# MarsCarrier_PWR.net
KiCad netlist of a schematic drawn in Altium Designer
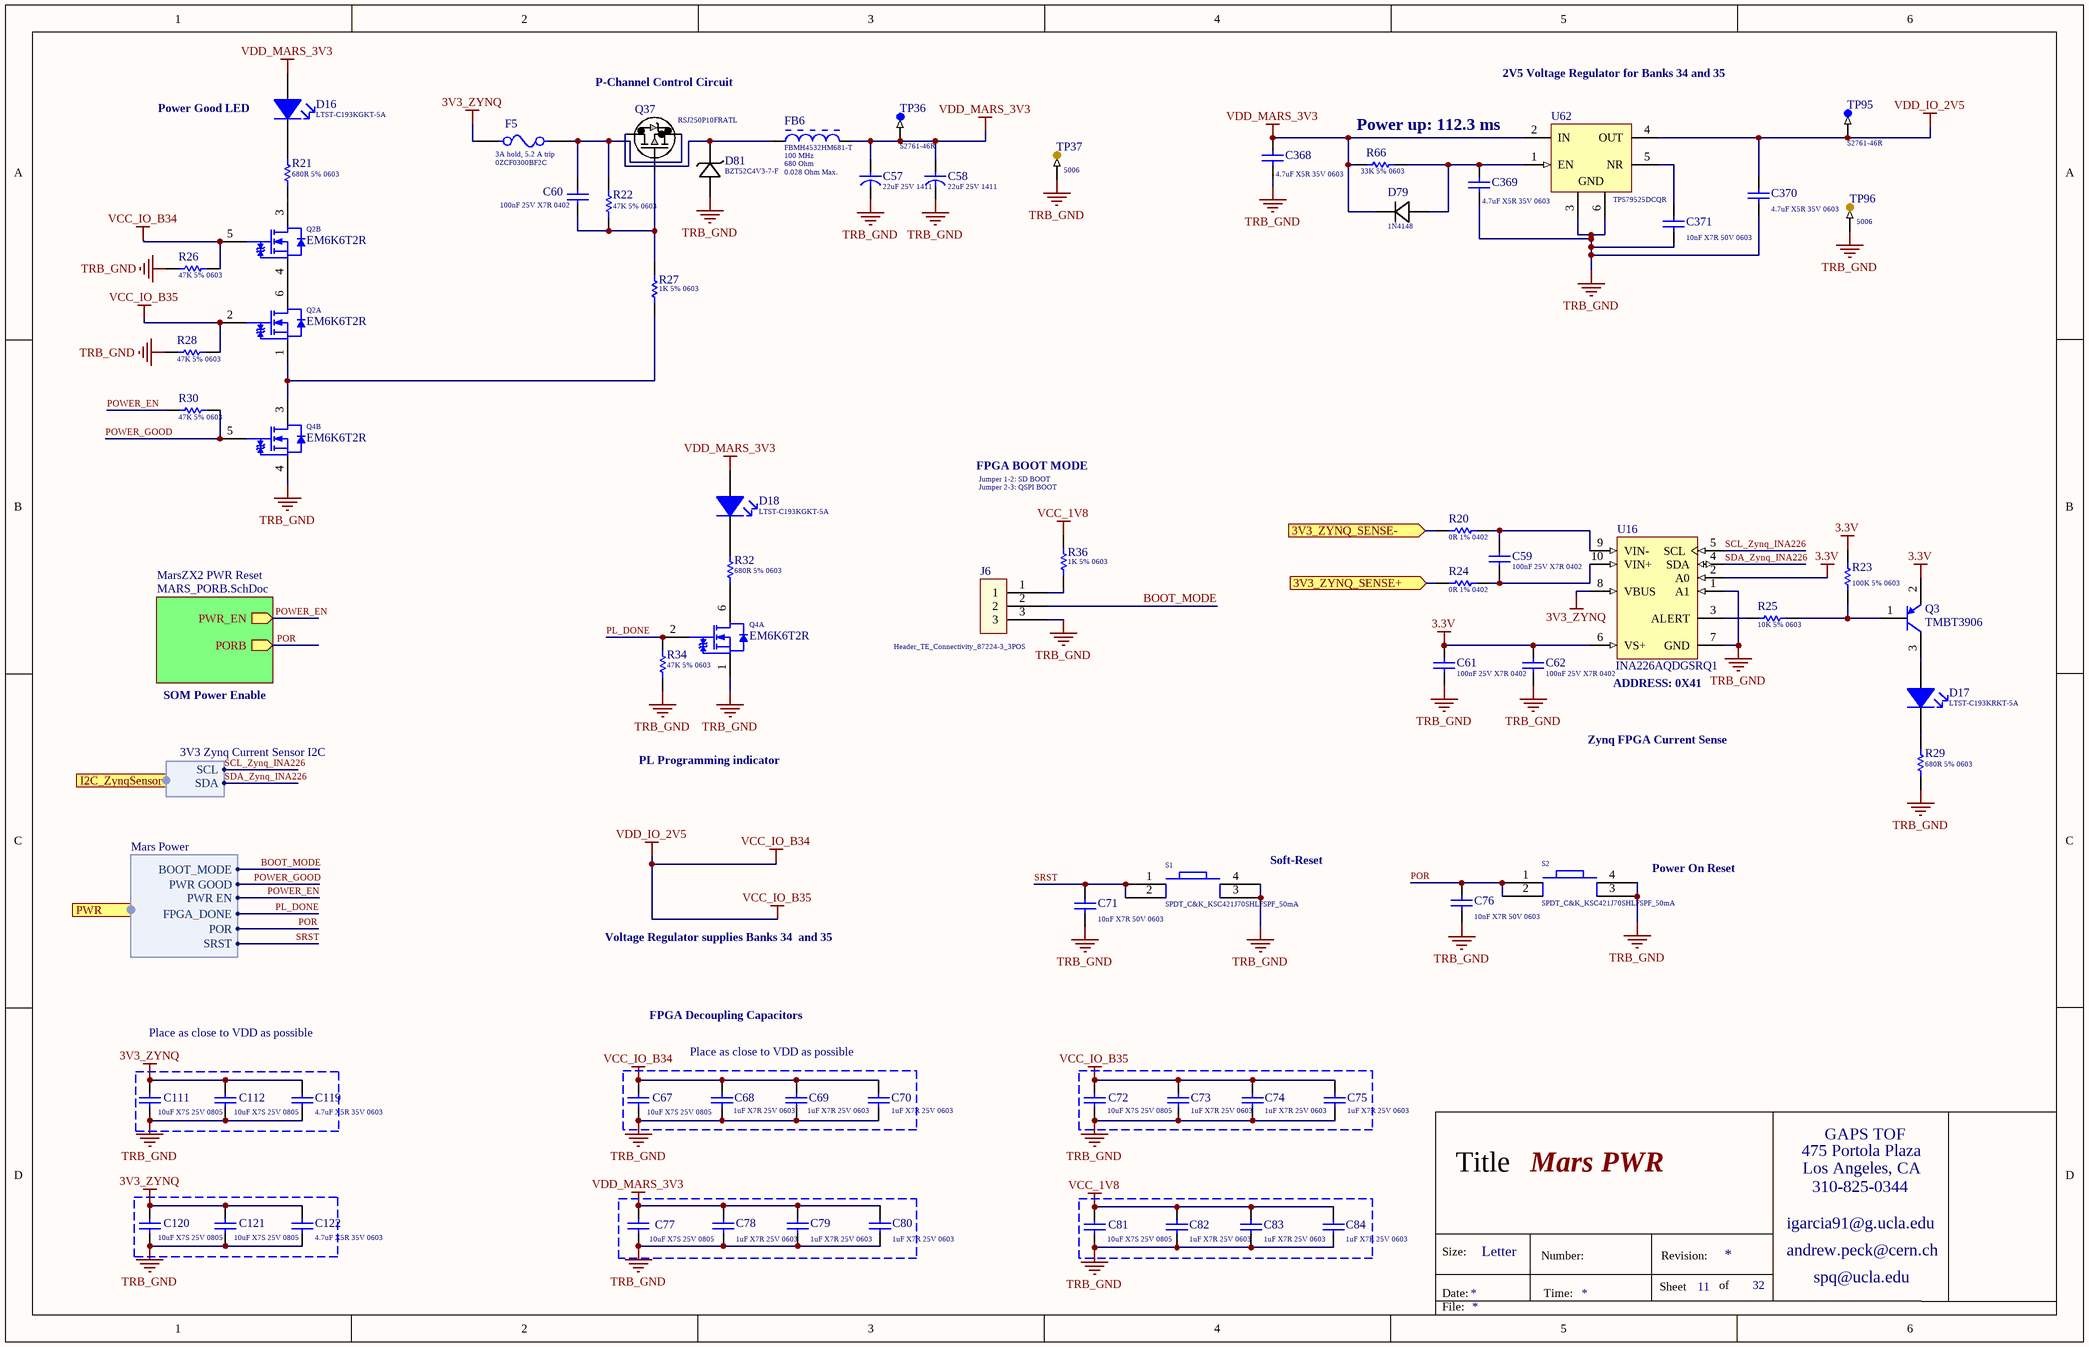
[diagram p0: MarsCarrier_PWR.SchDoc]

(export (version "E")
  (design (tool "Eeschema 10.0.6"))
  (components
    (comp (ref "C57")
      (value "Cap_Kemet_T521B226M025ATE100_22uF")
      (footprint "Cap_Kemet_T521B226M025ATE100_22uF")
      (description "Tantalum Capacitors - Polymer SMD 25V 22uF 1311 20% ESR=100mOhms")
      (fields (field (name "CAPACITANCE") "22uF 25V 1411"))
      (libsource (lib "Cap_Kemet_T521B226M025ATE100_22uF") (part "Cap_Kemet_T521B226M025ATE100_22uF"))
    )
    (comp (ref "C58")
      (value "Cap_Kemet_T521B226M025ATE100_22uF")
      (footprint "Cap_Kemet_T521B226M025ATE100_22uF")
      (description "Tantalum Capacitors - Polymer SMD 25V 22uF 1311 20% ESR=100mOhms")
      (fields (field (name "CAPACITANCE") "22uF 25V 1411"))
      (libsource (lib "Cap_Kemet_T521B226M025ATE100_22uF") (part "Cap_Kemet_T521B226M025ATE100_22uF"))
    )
    (comp (ref "C59")
      (value "Cap_Taiyo_Yuden_TMK105B7104KV-FR_100nF")
      (footprint "Cap_Taiyo_Yuden_TMK105B7104KV-FR_100nF")
      (description "CAP CER 100nF 25V X7R 0402")
      (fields (field (name "CAPACITANCE") "100nF 25V X7R 0402"))
      (libsource (lib "Cap_Taiyo_Yuden_TMK105B7104KV-FR_100nF") (part "Cap_Taiyo_Yuden_TMK105B7104KV-FR_100nF"))
    )
    (comp (ref "C60")
      (value "Cap_Taiyo_Yuden_TMK105B7104KV-FR_100nF")
      (footprint "Cap_Taiyo_Yuden_TMK105B7104KV-FR_100nF")
      (description "CAP CER 100nF 25V X7R 0402")
      (fields (field (name "CAPACITANCE") "100nF 25V X7R 0402"))
      (libsource (lib "Cap_Taiyo_Yuden_TMK105B7104KV-FR_100nF") (part "Cap_Taiyo_Yuden_TMK105B7104KV-FR_100nF"))
    )
    (comp (ref "C61")
      (value "Cap_Taiyo_Yuden_TMK105B7104KV-FR_100nF")
      (footprint "Cap_Taiyo_Yuden_TMK105B7104KV-FR_100nF")
      (description "CAP CER 100nF 25V X7R 0402")
      (fields (field (name "CAPACITANCE") "100nF 25V X7R 0402"))
      (libsource (lib "Cap_Taiyo_Yuden_TMK105B7104KV-FR_100nF") (part "Cap_Taiyo_Yuden_TMK105B7104KV-FR_100nF"))
    )
    (comp (ref "C62")
      (value "Cap_Taiyo_Yuden_TMK105B7104KV-FR_100nF")
      (footprint "Cap_Taiyo_Yuden_TMK105B7104KV-FR_100nF")
      (description "CAP CER 100nF 25V X7R 0402")
      (fields (field (name "CAPACITANCE") "100nF 25V X7R 0402"))
      (libsource (lib "Cap_Taiyo_Yuden_TMK105B7104KV-FR_100nF") (part "Cap_Taiyo_Yuden_TMK105B7104KV-FR_100nF"))
    )
    (comp (ref "C67")
      (value "Cap_Murata_ GRM21BC71E106ME11L_10uF")
      (footprint "Cap_Murata_ GRM21BC71E106ME11L_10uF")
      (description "CAP CER 10uF 25V X7R 0805")
      (fields (field (name "CAPACITANCE") "10uF X7S 25V 0805"))
      (libsource (lib "Cap_Murata_ GRM21BC71E106ME11L_10uF") (part "Cap_Murata_ GRM21BC71E106ME11L_10uF"))
    )
    (comp (ref "C68")
      (value "Cap_Murata_GCJ188R71E105KA01J_1uF")
      (footprint "Cap_Murata_GCJ188R71E105KA01J_1uF")
      (description "CAP CER 1uF 25V X7R 0603")
      (fields (field (name "CAPACITANCE") "1uF X7R 25V 0603"))
      (libsource (lib "Cap_Murata_GCJ188R71E105KA01J_1uF") (part "Cap_Murata_GCJ188R71E105KA01J_1uF"))
    )
    (comp (ref "C69")
      (value "Cap_Murata_GCJ188R71E105KA01J_1uF")
      (footprint "Cap_Murata_GCJ188R71E105KA01J_1uF")
      (description "CAP CER 1uF 25V X7R 0603")
      (fields (field (name "CAPACITANCE") "1uF X7R 25V 0603"))
      (libsource (lib "Cap_Murata_GCJ188R71E105KA01J_1uF") (part "Cap_Murata_GCJ188R71E105KA01J_1uF"))
    )
    (comp (ref "C70")
      (value "Cap_Murata_GCJ188R71E105KA01J_1uF")
      (footprint "Cap_Murata_GCJ188R71E105KA01J_1uF")
      (description "CAP CER 1uF 25V X7R 0603")
      (fields (field (name "CAPACITANCE") "1uF X7R 25V 0603"))
      (libsource (lib "Cap_Murata_GCJ188R71E105KA01J_1uF") (part "Cap_Murata_GCJ188R71E105KA01J_1uF"))
    )
    (comp (ref "C71")
      (value "Cap_Kemet_C0603C103J5RACTU_eec")
      (footprint "Kemet_C0603_0")
      (description "CAP CER 10nF 50V X7R 0603")
      (fields
        (field (name "PART NUMBER") "C0603C103J5RACTU")
        (field (name "MANUFACTURER") "Kemet")
        (field (name "CAPACITANCE") "10nF X7R 50V 0603")
      )
      (libsource (lib "Cap_Kemet_C0603C103J5RACTU_10nF") (part "Cap_Kemet_C0603C103J5RACTU_eec"))
    )
    (comp (ref "C72")
      (value "Cap_Murata_ GRM21BC71E106ME11L_10uF")
      (footprint "Cap_Murata_ GRM21BC71E106ME11L_10uF")
      (description "CAP CER 10uF 25V X7R 0805")
      (fields (field (name "CAPACITANCE") "10uF X7S 25V 0805"))
      (libsource (lib "Cap_Murata_ GRM21BC71E106ME11L_10uF") (part "Cap_Murata_ GRM21BC71E106ME11L_10uF"))
    )
    (comp (ref "C73")
      (value "Cap_Murata_GCJ188R71E105KA01J_1uF")
      (footprint "Cap_Murata_GCJ188R71E105KA01J_1uF")
      (description "CAP CER 1uF 25V X7R 0603")
      (fields (field (name "CAPACITANCE") "1uF X7R 25V 0603"))
      (libsource (lib "Cap_Murata_GCJ188R71E105KA01J_1uF") (part "Cap_Murata_GCJ188R71E105KA01J_1uF"))
    )
    (comp (ref "C74")
      (value "Cap_Murata_GCJ188R71E105KA01J_1uF")
      (footprint "Cap_Murata_GCJ188R71E105KA01J_1uF")
      (description "CAP CER 1uF 25V X7R 0603")
      (fields (field (name "CAPACITANCE") "1uF X7R 25V 0603"))
      (libsource (lib "Cap_Murata_GCJ188R71E105KA01J_1uF") (part "Cap_Murata_GCJ188R71E105KA01J_1uF"))
    )
    (comp (ref "C75")
      (value "Cap_Murata_GCJ188R71E105KA01J_1uF")
      (footprint "Cap_Murata_GCJ188R71E105KA01J_1uF")
      (description "CAP CER 1uF 25V X7R 0603")
      (fields (field (name "CAPACITANCE") "1uF X7R 25V 0603"))
      (libsource (lib "Cap_Murata_GCJ188R71E105KA01J_1uF") (part "Cap_Murata_GCJ188R71E105KA01J_1uF"))
    )
    (comp (ref "C76")
      (value "Cap_Kemet_C0603C103J5RACTU_eec")
      (footprint "Kemet_C0603_0")
      (description "CAP CER 10nF 50V X7R 0603")
      (fields
        (field (name "PART NUMBER") "C0603C103J5RACTU")
        (field (name "MANUFACTURER") "Kemet")
        (field (name "CAPACITANCE") "10nF X7R 50V 0603")
      )
      (libsource (lib "Cap_Kemet_C0603C103J5RACTU_10nF") (part "Cap_Kemet_C0603C103J5RACTU_eec"))
    )
    (comp (ref "C77")
      (value "Cap_Murata_ GRM21BC71E106ME11L_10uF")
      (footprint "Cap_Murata_ GRM21BC71E106ME11L_10uF")
      (description "CAP CER 10uF 25V X7R 0805")
      (fields (field (name "CAPACITANCE") "10uF X7S 25V 0805"))
      (libsource (lib "Cap_Murata_ GRM21BC71E106ME11L_10uF") (part "Cap_Murata_ GRM21BC71E106ME11L_10uF"))
    )
    (comp (ref "C78")
      (value "Cap_Murata_GCJ188R71E105KA01J_1uF")
      (footprint "Cap_Murata_GCJ188R71E105KA01J_1uF")
      (description "CAP CER 1uF 25V X7R 0603")
      (fields (field (name "CAPACITANCE") "1uF X7R 25V 0603"))
      (libsource (lib "Cap_Murata_GCJ188R71E105KA01J_1uF") (part "Cap_Murata_GCJ188R71E105KA01J_1uF"))
    )
    (comp (ref "C79")
      (value "Cap_Murata_GCJ188R71E105KA01J_1uF")
      (footprint "Cap_Murata_GCJ188R71E105KA01J_1uF")
      (description "CAP CER 1uF 25V X7R 0603")
      (fields (field (name "CAPACITANCE") "1uF X7R 25V 0603"))
      (libsource (lib "Cap_Murata_GCJ188R71E105KA01J_1uF") (part "Cap_Murata_GCJ188R71E105KA01J_1uF"))
    )
    (comp (ref "C80")
      (value "Cap_Murata_GCJ188R71E105KA01J_1uF")
      (footprint "Cap_Murata_GCJ188R71E105KA01J_1uF")
      (description "CAP CER 1uF 25V X7R 0603")
      (fields (field (name "CAPACITANCE") "1uF X7R 25V 0603"))
      (libsource (lib "Cap_Murata_GCJ188R71E105KA01J_1uF") (part "Cap_Murata_GCJ188R71E105KA01J_1uF"))
    )
    (comp (ref "C81")
      (value "Cap_Murata_ GRM21BC71E106ME11L_10uF")
      (footprint "Cap_Murata_ GRM21BC71E106ME11L_10uF")
      (description "CAP CER 10uF 25V X7R 0805")
      (fields (field (name "CAPACITANCE") "10uF X7S 25V 0805"))
      (libsource (lib "Cap_Murata_ GRM21BC71E106ME11L_10uF") (part "Cap_Murata_ GRM21BC71E106ME11L_10uF"))
    )
    (comp (ref "C82")
      (value "Cap_Murata_GCJ188R71E105KA01J_1uF")
      (footprint "Cap_Murata_GCJ188R71E105KA01J_1uF")
      (description "CAP CER 1uF 25V X7R 0603")
      (fields (field (name "CAPACITANCE") "1uF X7R 25V 0603"))
      (libsource (lib "Cap_Murata_GCJ188R71E105KA01J_1uF") (part "Cap_Murata_GCJ188R71E105KA01J_1uF"))
    )
    (comp (ref "C83")
      (value "Cap_Murata_GCJ188R71E105KA01J_1uF")
      (footprint "Cap_Murata_GCJ188R71E105KA01J_1uF")
      (description "CAP CER 1uF 25V X7R 0603")
      (fields (field (name "CAPACITANCE") "1uF X7R 25V 0603"))
      (libsource (lib "Cap_Murata_GCJ188R71E105KA01J_1uF") (part "Cap_Murata_GCJ188R71E105KA01J_1uF"))
    )
    (comp (ref "C84")
      (value "Cap_Murata_GCJ188R71E105KA01J_1uF")
      (footprint "Cap_Murata_GCJ188R71E105KA01J_1uF")
      (description "CAP CER 1uF 25V X7R 0603")
      (fields (field (name "CAPACITANCE") "1uF X7R 25V 0603"))
      (libsource (lib "Cap_Murata_GCJ188R71E105KA01J_1uF") (part "Cap_Murata_GCJ188R71E105KA01J_1uF"))
    )
    (comp (ref "C111")
      (value "Cap_Murata_ GRM21BC71E106ME11L_10uF")
      (footprint "Cap_Murata_ GRM21BC71E106ME11L_10uF")
      (description "CAP CER 10uF 25V X7R 0805")
      (fields (field (name "CAPACITANCE") "10uF X7S 25V 0805"))
      (libsource (lib "Cap_Murata_ GRM21BC71E106ME11L_10uF") (part "Cap_Murata_ GRM21BC71E106ME11L_10uF"))
    )
    (comp (ref "C112")
      (value "Cap_Murata_ GRM21BC71E106ME11L_10uF")
      (footprint "Cap_Murata_ GRM21BC71E106ME11L_10uF")
      (description "CAP CER 10uF 25V X7R 0805")
      (fields (field (name "CAPACITANCE") "10uF X7S 25V 0805"))
      (libsource (lib "Cap_Murata_ GRM21BC71E106ME11L_10uF") (part "Cap_Murata_ GRM21BC71E106ME11L_10uF"))
    )
    (comp (ref "C119")
      (value "Cap_Murata_ZRB18AR6YA475ME05L_4.7uF")
      (footprint "Cap_Murata_ZRB18AR6YA475ME05L_4.7uF")
      (description "CAP CER 4.7uF 35V X5R 0603")
      (fields (field (name "CAPACITANCE") "4.7uF X5R 35V 0603"))
      (libsource (lib "Cap_Murata_ZRB18AR6YA475ME05L_4.7uF") (part "Cap_Murata_ZRB18AR6YA475ME05L_4.7uF"))
    )
    (comp (ref "C120")
      (value "Cap_Murata_ GRM21BC71E106ME11L_10uF")
      (footprint "Cap_Murata_ GRM21BC71E106ME11L_10uF")
      (description "CAP CER 10uF 25V X7R 0805")
      (fields (field (name "CAPACITANCE") "10uF X7S 25V 0805"))
      (libsource (lib "Cap_Murata_ GRM21BC71E106ME11L_10uF") (part "Cap_Murata_ GRM21BC71E106ME11L_10uF"))
    )
    (comp (ref "C121")
      (value "Cap_Murata_ GRM21BC71E106ME11L_10uF")
      (footprint "Cap_Murata_ GRM21BC71E106ME11L_10uF")
      (description "CAP CER 10uF 25V X7R 0805")
      (fields (field (name "CAPACITANCE") "10uF X7S 25V 0805"))
      (libsource (lib "Cap_Murata_ GRM21BC71E106ME11L_10uF") (part "Cap_Murata_ GRM21BC71E106ME11L_10uF"))
    )
    (comp (ref "C122")
      (value "Cap_Murata_ZRB18AR6YA475ME05L_4.7uF")
      (footprint "Cap_Murata_ZRB18AR6YA475ME05L_4.7uF")
      (description "CAP CER 4.7uF 35V X5R 0603")
      (fields (field (name "CAPACITANCE") "4.7uF X5R 35V 0603"))
      (libsource (lib "Cap_Murata_ZRB18AR6YA475ME05L_4.7uF") (part "Cap_Murata_ZRB18AR6YA475ME05L_4.7uF"))
    )
    (comp (ref "C368")
      (value "Cap_Murata_ZRB18AR6YA475ME05L_4.7uF")
      (footprint "Cap_Murata_ZRB18AR6YA475ME05L_4.7uF")
      (description "CAP CER 4.7uF 35V X5R 0603")
      (fields (field (name "CAPACITANCE") "4.7uF X5R 35V 0603"))
      (libsource (lib "Cap_Murata_ZRB18AR6YA475ME05L_4.7uF") (part "Cap_Murata_ZRB18AR6YA475ME05L_4.7uF"))
    )
    (comp (ref "C369")
      (value "Cap_Murata_ZRB18AR6YA475ME05L_4.7uF")
      (footprint "Cap_Murata_ZRB18AR6YA475ME05L_4.7uF")
      (description "CAP CER 4.7uF 35V X5R 0603")
      (fields (field (name "CAPACITANCE") "4.7uF X5R 35V 0603"))
      (libsource (lib "Cap_Murata_ZRB18AR6YA475ME05L_4.7uF") (part "Cap_Murata_ZRB18AR6YA475ME05L_4.7uF"))
    )
    (comp (ref "C370")
      (value "Cap_Murata_ZRB18AR6YA475ME05L_4.7uF")
      (footprint "Cap_Murata_ZRB18AR6YA475ME05L_4.7uF")
      (description "CAP CER 4.7uF 35V X5R 0603")
      (fields (field (name "CAPACITANCE") "4.7uF X5R 35V 0603"))
      (libsource (lib "Cap_Murata_ZRB18AR6YA475ME05L_4.7uF") (part "Cap_Murata_ZRB18AR6YA475ME05L_4.7uF"))
    )
    (comp (ref "C371")
      (value "Cap_Kemet_C0603C103J5RACTU_eec")
      (footprint "Kemet_C0603_0")
      (description "CAP CER 10nF 50V X7R 0603")
      (fields
        (field (name "PART NUMBER") "C0603C103J5RACTU")
        (field (name "MANUFACTURER") "Kemet")
        (field (name "CAPACITANCE") "10nF X7R 50V 0603")
      )
      (libsource (lib "Cap_Kemet_C0603C103J5RACTU_10nF") (part "Cap_Kemet_C0603C103J5RACTU_eec"))
    )
    (comp (ref "D16")
      (value "Led_Lite-On_LTST-C193KGKT-5A_Green")
      (footprint "Led_Lite-On_LTST-C193KGKT-5A_Green")
      (description "Standard LEDs - SMD Green 470nm 28mcd 20mA")
      (fields (field (name "SERIES") "LTST-C193KGKT-5A"))
      (libsource (lib "Led_Lite-On_LTST-C193KGKT-5A_Green") (part "Led_Lite-On_LTST-C193KGKT-5A_Green"))
    )
    (comp (ref "D17")
      (value "LTST-C193KRKT-5A")
      (footprint "Led_Lite-On_LTST-C193KGKT-5A_Red")
      (description "Standard LEDs - SMD Red 470nm 28mcd 20mA")
      (fields (field (name "SERIES") "LTST-C193KRKT-5A"))
      (libsource (lib "Led_Lite-On_LTST-C193KGKT-5A_Red") (part "Led_Lite-On_LTST-C193KGKT-5A_Red"))
    )
    (comp (ref "D18")
      (value "Led_Lite-On_LTST-C193KGKT-5A_Green")
      (footprint "Led_Lite-On_LTST-C193KGKT-5A_Green")
      (description "Standard LEDs - SMD Green 470nm 28mcd 20mA")
      (fields (field (name "SERIES") "LTST-C193KGKT-5A"))
      (libsource (lib "Led_Lite-On_LTST-C193KGKT-5A_Green") (part "Led_Lite-On_LTST-C193KGKT-5A_Green"))
    )
    (comp (ref "D79")
      (value "Diode_ON_Semiconductor_1N4148WT_300mA")
      (footprint "Diode_ON_Semiconductor_1N4148WT_300mA")
      (description "Diodes - General Purpose, Power, Switching SINGLE JUNC. 75V 4.0NS COMP")
      (fields (field (name "SERIES") "1N4148"))
      (libsource (lib "Diode_ON_Semiconductor_1N4148WT_300mA") (part "Diode_ON_Semiconductor_1N4148WT_300mA"))
    )
    (comp (ref "D81")
      (value "BZT52C4V3-7-F")
      (footprint "SOD123")
      (description "Zener Diodes 500mW 4.3V Zener AEC-Q101 Qualified")
      (fields (field (name "SERIES") "BZT52C4V3-7-F"))
      (libsource (lib "4v3_zener_BZT52C4V3-7-F") (part "BZT52C4V3-7-F"))
    )
    (comp (ref "F5")
      (value "3A hold, 5.2 A trip")
      (footprint "Bel_0ZCF_MFG")
      (description "Resettable Fuses - PPTC 3A 24V PPTC 2920 SMD")
      (fields (field (name "SERIES") "0ZCF0300BF2C"))
      (libsource (lib "Fuse_Bel_0ZCF0300BF2C_3A_hold") (part "0ZCF0300BF2C"))
    )
    (comp (ref "FB6")
      (value "FBMH4532HM681-T")
      (footprint "TAYO-FBMH4532-2_V")
      (fields
        (field (name "PARTNUMBER") "FBMH4532HM681-T")
        (field (name "MANUFACTURER") "Taiyo Yuden")
        (field (name "MEASURING FREQUENCY") "100 MHz")
        (field (name "NOMINAL IMPEDANCE") "680 Ohm")
        (field (name "DC RESISTANCE") "0.028 Ohm Max.")
      )
      (libsource (lib "Taiyo_Yuden_FBMH4532HM681") (part "FBMH4532HM681-T"))
    )
    (comp (ref "J6")
      (value "Header_TE_Connectivity_87224-3_3POS")
      (footprint "Header_TE_Connectivity_87224-3_3POS")
      (description "Headers & Wire Housings UNSHRD VERT SNGL 3")
      (libsource (lib "Header_TE_Connectivity_87224-3_3POS") (part "Header_TE_Connectivity_87224-3_3POS"))
    )
    (comp (ref "Q2")
      (value "Mos_ROHM_EM6K6T2R_N_300mA")
      (footprint "Mos_ROHM_EM6K6T2R_N_300mA:Mos_ROHM_EM6K6T2R_N_300mA")
      (description "MOSFET Small Signal Dual N-CH 20V .3A .15W")
      (fields (field (name "SERIES") "EM6K6T2R"))
      (libsource (lib "Mos_ROHM_EM6K6T2R_N_300mA") (part "Mos_ROHM_EM6K6T2R_N_300mA"))
    )
    (comp (ref "Q3")
      (value "BJT_PNP_Toshiba_TMBT3906")
      (footprint "BJT_PNP_Toshiba_TMBT3906")
      (description "Bipolar Transistors - BJT Transistor for Low Freq. Amplification")
      (fields (field (name "SERIES") "TMBT3906"))
      (libsource (lib "BJT_PNP_Toshiba_TMBT3906") (part "BJT_PNP_Toshiba_TMBT3906"))
    )
    (comp (ref "Q4")
      (value "Mos_ROHM_EM6K6T2R_N_300mA")
      (footprint "Mos_ROHM_EM6K6T2R_N_300mA:Mos_ROHM_EM6K6T2R_N_300mA")
      (description "MOSFET Small Signal Dual N-CH 20V .3A .15W")
      (fields (field (name "SERIES") "EM6K6T2R"))
      (libsource (lib "Mos_ROHM_EM6K6T2R_N_300mA") (part "Mos_ROHM_EM6K6T2R_N_300mA"))
    )
    (comp (ref "Q37")
      (value "Mos_ROHM_RSJ250P10FRATL_25A")
      (footprint "Mos_ROHM_RSJ250P10FRATL_25A")
      (description "MOSFET Pch -100V Vds -25A 0.05Rds(on) 60Qg")
      (fields (field (name "SERIES") "RSJ250P10FRATL"))
      (libsource (lib "Mos_ROHM_RSJ250P10FRATL_25A") (part "Mos_ROHM_RSJ250P10FRATL_25A"))
    )
    (comp (ref "R20")
      (value "Res_Vishay_CRCW04020000Z0EDC_0_Ohm")
      (footprint "Res_Vishay_CRCW04020000Z0EDC_0_Ohm")
      (description "0R 0.062W 1% 0402 (1005 Metric)  SMD")
      (fields (field (name "RESISTANCE") "0R 1% 0402"))
      (libsource (lib "Res_Vishay_CRCW04020000Z0EDC_0_Ohm") (part "Res_Vishay_CRCW04020000Z0EDC_0_Ohm"))
    )
    (comp (ref "R21")
      (value "680R 5% 0603")
      (footprint "RESC0603(1608)_L")
      (description "680R 0.1W 5% 0603 (1608 Metric)  SMD")
      (fields (field (name "TOLERANCE") "5 %") (field (name "POWER") "0.1 W"))
      (libsource (lib "Altium Content Vault") (part "RES"))
    )
    (comp (ref "R22")
      (value "47K 5% 0603")
      (footprint "RESC0603(1608)_L")
      (description "47K 0.1W 5% 0603 (1608 Metric)  SMD")
      (fields (field (name "TOLERANCE") "5 %") (field (name "POWER") "0.1 W"))
      (libsource (lib "Altium Content Vault") (part "RES"))
    )
    (comp (ref "R23")
      (value "100K 5% 0603")
      (footprint "RESC0603(1608)_N")
      (description "100K 0.1W 5% 0603 (1608 Metric)  SMD")
      (fields (field (name "TOLERANCE") "5 %") (field (name "POWER") "0.1 W"))
      (libsource (lib "Altium Content Vault") (part "RES"))
    )
    (comp (ref "R24")
      (value "Res_Vishay_CRCW04020000Z0EDC_0_Ohm")
      (footprint "Res_Vishay_CRCW04020000Z0EDC_0_Ohm")
      (description "0R 0.062W 1% 0402 (1005 Metric)  SMD")
      (fields (field (name "RESISTANCE") "0R 1% 0402"))
      (libsource (lib "Res_Vishay_CRCW04020000Z0EDC_0_Ohm") (part "Res_Vishay_CRCW04020000Z0EDC_0_Ohm"))
    )
    (comp (ref "R25")
      (value "10K 5% 0603")
      (footprint "RESC0603(1608)_L")
      (description "10K 0.1W 5% 0603 (1608 Metric)  SMD")
      (fields (field (name "TOLERANCE") "5 %") (field (name "POWER") "0.1 W"))
      (libsource (lib "Altium Content Vault") (part "RES"))
    )
    (comp (ref "R26")
      (value "47K 5% 0603")
      (footprint "RESC0603(1608)_L")
      (description "47K 0.1W 5% 0603 (1608 Metric)  SMD")
      (fields (field (name "TOLERANCE") "5 %") (field (name "POWER") "0.1 W"))
      (libsource (lib "Altium Content Vault") (part "RES"))
    )
    (comp (ref "R27")
      (value "1K 5% 0603")
      (footprint "RESC0603(1608)_L")
      (description "1K 0.1W 5% 0603 (1608 Metric)  SMD")
      (fields (field (name "TOLERANCE") "5 %") (field (name "POWER") "0.1 W"))
      (libsource (lib "Altium Content Vault") (part "RES"))
    )
    (comp (ref "R28")
      (value "47K 5% 0603")
      (footprint "RESC0603(1608)_L")
      (description "47K 0.1W 5% 0603 (1608 Metric)  SMD")
      (fields (field (name "TOLERANCE") "5 %") (field (name "POWER") "0.1 W"))
      (libsource (lib "Altium Content Vault") (part "RES"))
    )
    (comp (ref "R29")
      (value "680R 5% 0603")
      (footprint "RESC0603(1608)_L")
      (description "680R 0.1W 5% 0603 (1608 Metric)  SMD")
      (fields (field (name "TOLERANCE") "5 %") (field (name "POWER") "0.1 W"))
      (libsource (lib "Altium Content Vault") (part "RES"))
    )
    (comp (ref "R30")
      (value "47K 5% 0603")
      (footprint "RESC0603(1608)_L")
      (description "47K 0.1W 5% 0603 (1608 Metric)  SMD")
      (fields (field (name "TOLERANCE") "5 %") (field (name "POWER") "0.1 W"))
      (libsource (lib "Altium Content Vault") (part "RES"))
    )
    (comp (ref "R32")
      (value "680R 5% 0603")
      (footprint "RESC0603(1608)_L")
      (description "680R 0.1W 5% 0603 (1608 Metric)  SMD")
      (fields (field (name "TOLERANCE") "5 %") (field (name "POWER") "0.1 W"))
      (libsource (lib "Altium Content Vault") (part "RES"))
    )
    (comp (ref "R34")
      (value "47K 5% 0603")
      (footprint "RESC0603(1608)_L")
      (description "47K 0.1W 5% 0603 (1608 Metric)  SMD")
      (fields (field (name "TOLERANCE") "5 %") (field (name "POWER") "0.1 W"))
      (libsource (lib "Altium Content Vault") (part "RES"))
    )
    (comp (ref "R36")
      (value "1K 5% 0603")
      (footprint "RESC0603(1608)_L")
      (description "1K 0.1W 5% 0603 (1608 Metric)  SMD")
      (fields (field (name "TOLERANCE") "5 %") (field (name "POWER") "0.1 W"))
      (libsource (lib "Altium Content Vault") (part "RES"))
    )
    (comp (ref "R66")
      (value "33K 5% 0603")
      (footprint "RESC0603(1608)_L")
      (description "33K 0.1W 5% 0603 (1608 Metric)  SMD")
      (fields (field (name "TOLERANCE") "5 %") (field (name "POWER") "0.1 W"))
      (libsource (lib "Altium Content Vault") (part "RES"))
    )
    (comp (ref "S1")
      (value "SPDT_C&K_KSC421J70SHLFSPF_50mA")
      (footprint "SPDT_C&K_KSC421J70SHLFSPF_50mA")
      (description "Tactile Switches Tact 6.2 x 6.2, 5.1 mm H, 1.7N, J leads, Potting Friendly, IP67")
      (libsource (lib "SPDT_C&K_KSC421J70SHLFSPF_50mA") (part "SPDT_C&K_KSC421J70SHLFSPF_50mA"))
    )
    (comp (ref "S2")
      (value "SPDT_C&K_KSC421J70SHLFSPF_50mA")
      (footprint "SPDT_C&K_KSC421J70SHLFSPF_50mA")
      (description "Tactile Switches Tact 6.2 x 6.2, 5.1 mm H, 1.7N, J leads, Potting Friendly, IP67")
      (libsource (lib "SPDT_C&K_KSC421J70SHLFSPF_50mA") (part "SPDT_C&K_KSC421J70SHLFSPF_50mA"))
    )
    (comp (ref "TP36")
      (value "TP_Harwin_S2761_46R")
      (footprint "TP_Harwin_S2761_46R")
      (description "Circuit Board Hardware - PCB SMT Mini Test Terminal, Reel")
      (fields (field (name "SERIES") "S2761-46R"))
      (libsource (lib "TP_Harwin_S2761_46R") (part "TP_Harwin_S2761_46R"))
    )
    (comp (ref "TP37")
      (value "TP_Keystone_Electronics_5006")
      (footprint "TP_Keystone_Electronics_5006")
      (description "Circuit Board Hardware - PCB TEST POINT BLK .063")
      (fields (field (name "SERIES") "5006"))
      (libsource (lib "TP_Keystone_Electronics_5006") (part "TP_Keystone_Electronics_5006"))
    )
    (comp (ref "TP95")
      (value "TP_Harwin_S2761_46R")
      (footprint "TP_Harwin_S2761_46R")
      (description "Circuit Board Hardware - PCB SMT Mini Test Terminal, Reel")
      (fields (field (name "SERIES") "S2761-46R"))
      (libsource (lib "TP_Harwin_S2761_46R") (part "TP_Harwin_S2761_46R"))
    )
    (comp (ref "TP96")
      (value "TP_Keystone_Electronics_5006")
      (footprint "TP_Keystone_Electronics_5006")
      (description "Circuit Board Hardware - PCB TEST POINT BLK .063")
      (fields (field (name "SERIES") "5006"))
      (libsource (lib "TP_Keystone_Electronics_5006") (part "TP_Keystone_Electronics_5006"))
    )
    (comp (ref "U16")
      (value "INA226AQDGSRQ1")
      (footprint "INA226AQDGSRQ1")
      (libsource (lib "INA226AQDGSRQ1") (part "INA226AQDGSRQ1"))
    )
    (comp (ref "U62")
      (value "TPS79525DCQR")
      (footprint "DCQ0006A_L")
      (fields (field (name "MANUFACTURER") "Texas Instruments"))
      (libsource (lib "TPS79525DCQR") (part "CMP-0395-00444-2"))
    )
  )
  (nets
    (net (code "8") (name "/3V3_ZYNQ_SENSE+") (class "Default")
      (node (ref "R24") (pin "1") (pinfunction "1_1") (pintype "passive"))
    )
    (net (code "9") (name "/3V3_ZYNQ_SENSE-") (class "Default")
      (node (ref "R20") (pin "1") (pinfunction "1_1") (pintype "passive"))
    )
    (net (code "10") (name "/BOOT_MODE") (class "Default")
      (node (ref "J6") (pin "2") (pinfunction "2_2") (pintype "passive"))
    )
    (net (code "11") (name "/PL_DONE") (class "Default")
      (node (ref "Q4") (pin "2") (pinfunction "G_2") (pintype "passive"))
      (node (ref "R34") (pin "2") (pinfunction "2_2") (pintype "passive"))
    )
    (net (code "12") (name "/POR") (class "Default")
      (node (ref "C76") (pin "1") (pinfunction "1_1") (pintype "passive"))
      (node (ref "S2") (pin "1") (pintype "passive"))
      (node (ref "S2") (pin "2") (pintype "passive"))
    )
    (net (code "13") (name "/POWER_EN") (class "Default")
      (node (ref "R30") (pin "2") (pinfunction "2_2") (pintype "passive"))
    )
    (net (code "14") (name "/POWER_GOOD") (class "Default")
      (node (ref "Q4") (pin "5") (pinfunction "G_5") (pintype "passive"))
      (node (ref "R30") (pin "1") (pinfunction "1_1") (pintype "passive"))
    )
    (net (code "15") (name "/SCL_Zynq_INA226") (class "Default")
      (node (ref "U16") (pin "5") (pinfunction "SCL_5") (pintype "input"))
    )
    (net (code "16") (name "/SDA_Zynq_INA226") (class "Default")
      (node (ref "U16") (pin "4") (pinfunction "SDA_4") (pintype "bidirectional"))
    )
    (net (code "17") (name "/SRST") (class "Default")
      (node (ref "C71") (pin "1") (pinfunction "1_1") (pintype "passive"))
      (node (ref "S1") (pin "1") (pintype "passive"))
      (node (ref "S1") (pin "2") (pintype "passive"))
    )
    (net (code "20") (name "3.3V") (class "Default")
      (node (ref "C61") (pin "2") (pinfunction "2_2") (pintype "passive"))
      (node (ref "C62") (pin "2") (pinfunction "2_2") (pintype "passive"))
      (node (ref "Q3") (pin "2") (pinfunction "E_2") (pintype "passive"))
      (node (ref "R23") (pin "2") (pinfunction "2_2") (pintype "passive"))
      (node (ref "U16") (pin "2") (pinfunction "A0_2") (pintype "input"))
      (node (ref "U16") (pin "6") (pinfunction "VS+_6") (pintype "input"))
    )
    (net (code "21") (name "3V3_ZYNQ") (class "Default")
      (node (ref "C111") (pin "1") (pinfunction "1_1") (pintype "passive"))
      (node (ref "C112") (pin "1") (pinfunction "1_1") (pintype "passive"))
      (node (ref "C119") (pin "1") (pinfunction "1_1") (pintype "passive"))
      (node (ref "C120") (pin "1") (pinfunction "1_1") (pintype "passive"))
      (node (ref "C121") (pin "1") (pinfunction "1_1") (pintype "passive"))
      (node (ref "C122") (pin "1") (pinfunction "1_1") (pintype "passive"))
      (node (ref "F5") (pin "1") (pinfunction "1_1") (pintype "passive"))
      (node (ref "U16") (pin "8") (pinfunction "VBUS_8") (pintype "input"))
    )
    (net (code "22") (name "Net-(D16-K)") (class "Default")
      (node (ref "D16") (pin "1") (pinfunction "K_1") (pintype "passive"))
      (node (ref "R21") (pin "2") (pinfunction "2_2") (pintype "passive"))
    )
    (net (code "23") (name "Net-(D17-A)") (class "Default")
      (node (ref "D17") (pin "2") (pinfunction "A_2") (pintype "passive"))
      (node (ref "Q3") (pin "3") (pinfunction "C_3") (pintype "passive"))
    )
    (net (code "24") (name "Net-(D17-K)") (class "Default")
      (node (ref "D17") (pin "1") (pinfunction "K_1") (pintype "passive"))
      (node (ref "R29") (pin "2") (pinfunction "2_2") (pintype "passive"))
    )
    (net (code "25") (name "Net-(D18-K)") (class "Default")
      (node (ref "D18") (pin "1") (pinfunction "K_1") (pintype "passive"))
      (node (ref "R32") (pin "2") (pinfunction "2_2") (pintype "passive"))
    )
    (net (code "26") (name "Net-(J6-Pad1)") (class "Default")
      (node (ref "J6") (pin "1") (pinfunction "1_1") (pintype "passive"))
      (node (ref "R36") (pin "1") (pinfunction "1_1") (pintype "passive"))
    )
    (net (code "27") (name "Net-(Q2A-D)") (class "Default")
      (node (ref "Q2") (pin "4") (pinfunction "S_4") (pintype "passive"))
      (node (ref "Q2") (pin "6") (pinfunction "D_6") (pintype "passive"))
    )
    (net (code "28") (name "Net-(Q2A-S)") (class "Default")
      (node (ref "Q2") (pin "1") (pinfunction "S_1") (pintype "passive"))
      (node (ref "Q4") (pin "3") (pinfunction "D_3") (pintype "passive"))
      (node (ref "R27") (pin "1") (pinfunction "1_1") (pintype "passive"))
    )
    (net (code "29") (name "Net-(Q2B-D)") (class "Default")
      (node (ref "Q2") (pin "3") (pinfunction "D_3") (pintype "passive"))
      (node (ref "R21") (pin "1") (pinfunction "1_1") (pintype "passive"))
    )
    (net (code "30") (name "Net-(Q3-B)") (class "Default")
      (node (ref "Q3") (pin "1") (pinfunction "B_1") (pintype "passive"))
      (node (ref "R23") (pin "1") (pinfunction "1_1") (pintype "passive"))
      (node (ref "R25") (pin "1") (pinfunction "1_1") (pintype "passive"))
    )
    (net (code "31") (name "Net-(Q4A-D)") (class "Default")
      (node (ref "Q4") (pin "6") (pinfunction "D_6") (pintype "passive"))
      (node (ref "R32") (pin "1") (pinfunction "1_1") (pintype "passive"))
    )
    (net (code "32") (name "Net-(Q37-D)") (class "Default")
      (node (ref "D81") (pin "1") (pinfunction "1_1") (pintype "passive"))
      (node (ref "FB6") (pin "1") (pinfunction "1_1") (pintype "passive"))
      (node (ref "Q37") (pin "2") (pinfunction "D_2") (pintype "passive"))
    )
    (net (code "33") (name "Net-(Q37-G)") (class "Default")
      (node (ref "C60") (pin "1") (pinfunction "1_1") (pintype "passive"))
      (node (ref "Q37") (pin "1") (pinfunction "G_1") (pintype "passive"))
      (node (ref "R22") (pin "1") (pinfunction "1_1") (pintype "passive"))
      (node (ref "R27") (pin "2") (pinfunction "2_2") (pintype "passive"))
    )
    (net (code "34") (name "Net-(Q37-S)") (class "Default")
      (node (ref "C60") (pin "2") (pinfunction "2_2") (pintype "passive"))
      (node (ref "F5") (pin "2") (pinfunction "2_2") (pintype "passive"))
      (node (ref "Q37") (pin "3") (pinfunction "S_3") (pintype "passive"))
      (node (ref "R22") (pin "2") (pinfunction "2_2") (pintype "passive"))
    )
    (net (code "35") (name "Net-(U16-ALERT)") (class "Default")
      (node (ref "R25") (pin "2") (pinfunction "2_2") (pintype "passive"))
      (node (ref "U16") (pin "3") (pinfunction "ALERT_3") (pintype "open_collector"))
    )
    (net (code "36") (name "Net-(U16-VIN+)") (class "Default")
      (node (ref "C59") (pin "1") (pinfunction "1_1") (pintype "passive"))
      (node (ref "R24") (pin "2") (pinfunction "2_2") (pintype "passive"))
      (node (ref "U16") (pin "10") (pinfunction "VIN+_10") (pintype "input"))
    )
    (net (code "37") (name "Net-(U16-VIN-)") (class "Default")
      (node (ref "C59") (pin "2") (pinfunction "2_2") (pintype "passive"))
      (node (ref "R20") (pin "2") (pinfunction "2_2") (pintype "passive"))
      (node (ref "U16") (pin "9") (pinfunction "VIN-_9") (pintype "input"))
    )
    (net (code "38") (name "Net-(U62-EN)") (class "Default")
      (node (ref "C369") (pin "2") (pinfunction "2_2") (pintype "passive"))
      (node (ref "D79") (pin "2") (pinfunction "2_2") (pintype "passive"))
      (node (ref "R66") (pin "2") (pinfunction "2_2") (pintype "passive"))
      (node (ref "U62") (pin "1") (pinfunction "EN_1") (pintype "input"))
    )
    (net (code "39") (name "Net-(U62-NR)") (class "Default")
      (node (ref "C371") (pin "1") (pinfunction "1_1") (pintype "passive"))
      (node (ref "U62") (pin "5") (pinfunction "NR_5") (pintype "passive"))
    )
    (net (code "40") (name "TRB_GND") (class "Default")
      (node (ref "C111") (pin "2") (pinfunction "2_2") (pintype "passive"))
      (node (ref "C112") (pin "2") (pinfunction "2_2") (pintype "passive"))
      (node (ref "C119") (pin "2") (pinfunction "2_2") (pintype "passive"))
      (node (ref "C120") (pin "2") (pinfunction "2_2") (pintype "passive"))
      (node (ref "C121") (pin "2") (pinfunction "2_2") (pintype "passive"))
      (node (ref "C122") (pin "2") (pinfunction "2_2") (pintype "passive"))
      (node (ref "C368") (pin "1") (pinfunction "1_1") (pintype "passive"))
      (node (ref "C369") (pin "1") (pinfunction "1_1") (pintype "passive"))
      (node (ref "C370") (pin "1") (pinfunction "1_1") (pintype "passive"))
      (node (ref "C371") (pin "2") (pinfunction "2_2") (pintype "passive"))
      (node (ref "C57") (pin "2") (pinfunction "2_2") (pintype "passive"))
      (node (ref "C58") (pin "2") (pinfunction "2_2") (pintype "passive"))
      (node (ref "C61") (pin "1") (pinfunction "1_1") (pintype "passive"))
      (node (ref "C62") (pin "1") (pinfunction "1_1") (pintype "passive"))
      (node (ref "C67") (pin "2") (pinfunction "2_2") (pintype "passive"))
      (node (ref "C68") (pin "1") (pinfunction "1_1") (pintype "passive"))
      (node (ref "C69") (pin "1") (pinfunction "1_1") (pintype "passive"))
      (node (ref "C70") (pin "1") (pinfunction "1_1") (pintype "passive"))
      (node (ref "C71") (pin "2") (pinfunction "2_2") (pintype "passive"))
      (node (ref "C72") (pin "2") (pinfunction "2_2") (pintype "passive"))
      (node (ref "C73") (pin "1") (pinfunction "1_1") (pintype "passive"))
      (node (ref "C74") (pin "1") (pinfunction "1_1") (pintype "passive"))
      (node (ref "C75") (pin "1") (pinfunction "1_1") (pintype "passive"))
      (node (ref "C76") (pin "2") (pinfunction "2_2") (pintype "passive"))
      (node (ref "C77") (pin "2") (pinfunction "2_2") (pintype "passive"))
      (node (ref "C78") (pin "1") (pinfunction "1_1") (pintype "passive"))
      (node (ref "C79") (pin "1") (pinfunction "1_1") (pintype "passive"))
      (node (ref "C80") (pin "1") (pinfunction "1_1") (pintype "passive"))
      (node (ref "C81") (pin "2") (pinfunction "2_2") (pintype "passive"))
      (node (ref "C82") (pin "1") (pinfunction "1_1") (pintype "passive"))
      (node (ref "C83") (pin "1") (pinfunction "1_1") (pintype "passive"))
      (node (ref "C84") (pin "1") (pinfunction "1_1") (pintype "passive"))
      (node (ref "D81") (pin "2") (pinfunction "2_2") (pintype "passive"))
      (node (ref "J6") (pin "3") (pinfunction "3_3") (pintype "passive"))
      (node (ref "Q4") (pin "1") (pinfunction "S_1") (pintype "passive"))
      (node (ref "Q4") (pin "4") (pinfunction "S_4") (pintype "passive"))
      (node (ref "R26") (pin "2") (pinfunction "2_2") (pintype "passive"))
      (node (ref "R28") (pin "2") (pinfunction "2_2") (pintype "passive"))
      (node (ref "R29") (pin "1") (pinfunction "1_1") (pintype "passive"))
      (node (ref "R34") (pin "1") (pinfunction "1_1") (pintype "passive"))
      (node (ref "S1") (pin "3") (pintype "passive"))
      (node (ref "S1") (pin "4") (pintype "passive"))
      (node (ref "S2") (pin "3") (pintype "passive"))
      (node (ref "S2") (pin "4") (pintype "passive"))
      (node (ref "TP37") (pin "1") (pinfunction "1_1") (pintype "input"))
      (node (ref "TP96") (pin "1") (pinfunction "1_1") (pintype "input"))
      (node (ref "U16") (pin "1") (pinfunction "A1_1") (pintype "input"))
      (node (ref "U16") (pin "7") (pinfunction "GND_7") (pintype "power_in"))
      (node (ref "U62") (pin "3") (pinfunction "GND_3") (pintype "power_in"))
      (node (ref "U62") (pin "6") (pinfunction "GND_6") (pintype "power_in"))
    )
    (net (code "41") (name "VCC_1V8") (class "Default")
      (node (ref "C81") (pin "1") (pinfunction "1_1") (pintype "passive"))
      (node (ref "C82") (pin "2") (pinfunction "2_2") (pintype "passive"))
      (node (ref "C83") (pin "2") (pinfunction "2_2") (pintype "passive"))
      (node (ref "C84") (pin "2") (pinfunction "2_2") (pintype "passive"))
      (node (ref "R36") (pin "2") (pinfunction "2_2") (pintype "passive"))
    )
    (net (code "42") (name "VCC_IO_B34") (class "Default")
      (node (ref "C370") (pin "2") (pinfunction "2_2") (pintype "passive"))
      (node (ref "C67") (pin "1") (pinfunction "1_1") (pintype "passive"))
      (node (ref "C68") (pin "2") (pinfunction "2_2") (pintype "passive"))
      (node (ref "C69") (pin "2") (pinfunction "2_2") (pintype "passive"))
      (node (ref "C70") (pin "2") (pinfunction "2_2") (pintype "passive"))
      (node (ref "C72") (pin "1") (pinfunction "1_1") (pintype "passive"))
      (node (ref "C73") (pin "2") (pinfunction "2_2") (pintype "passive"))
      (node (ref "C74") (pin "2") (pinfunction "2_2") (pintype "passive"))
      (node (ref "C75") (pin "2") (pinfunction "2_2") (pintype "passive"))
      (node (ref "Q2") (pin "2") (pinfunction "G_2") (pintype "passive"))
      (node (ref "Q2") (pin "5") (pinfunction "G_5") (pintype "passive"))
      (node (ref "R26") (pin "1") (pinfunction "1_1") (pintype "passive"))
      (node (ref "R28") (pin "1") (pinfunction "1_1") (pintype "passive"))
      (node (ref "TP95") (pin "1") (pinfunction "1_1") (pintype "input"))
      (node (ref "U62") (pin "4") (pinfunction "OUT_4") (pintype "power_in"))
    )
    (net (code "43") (name "VDD_MARS_3V3") (class "Default")
      (node (ref "C368") (pin "2") (pinfunction "2_2") (pintype "passive"))
      (node (ref "C57") (pin "1") (pinfunction "1_1") (pintype "passive"))
      (node (ref "C58") (pin "1") (pinfunction "1_1") (pintype "passive"))
      (node (ref "C77") (pin "1") (pinfunction "1_1") (pintype "passive"))
      (node (ref "C78") (pin "2") (pinfunction "2_2") (pintype "passive"))
      (node (ref "C79") (pin "2") (pinfunction "2_2") (pintype "passive"))
      (node (ref "C80") (pin "2") (pinfunction "2_2") (pintype "passive"))
      (node (ref "D16") (pin "2") (pinfunction "A_2") (pintype "passive"))
      (node (ref "D18") (pin "2") (pinfunction "A_2") (pintype "passive"))
      (node (ref "D79") (pin "1") (pinfunction "1_1") (pintype "passive"))
      (node (ref "FB6") (pin "2") (pinfunction "2_2") (pintype "passive"))
      (node (ref "R66") (pin "1") (pinfunction "1_1") (pintype "passive"))
      (node (ref "TP36") (pin "1") (pinfunction "1_1") (pintype "input"))
      (node (ref "U62") (pin "2") (pinfunction "IN_2") (pintype "power_in"))
    )
  )
)
